# scout_schematics_v0.net
KiCad netlist of a schematic drawn in EAGLE
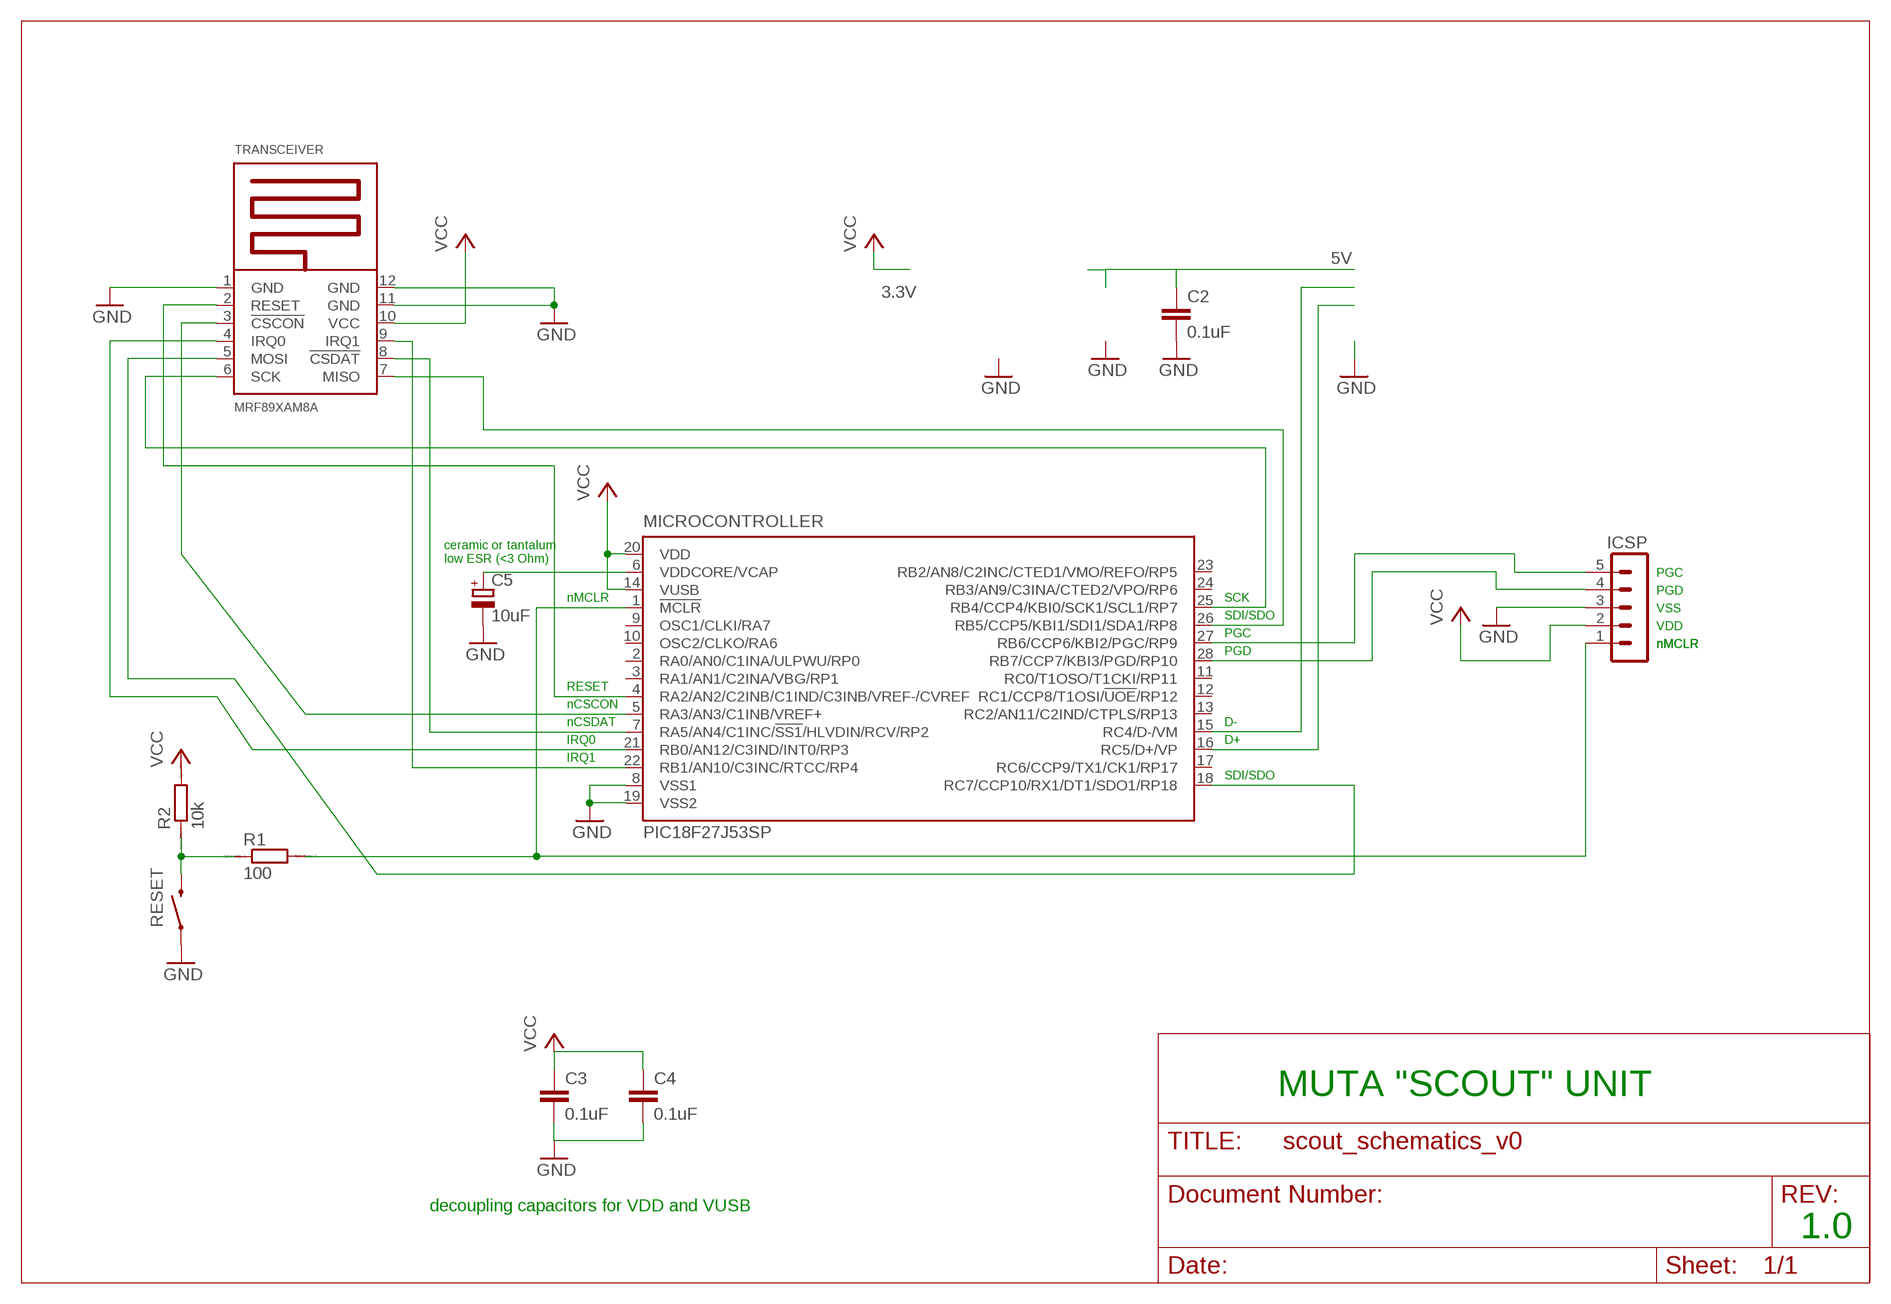
[diagram p0: schematic, sheet 1]

(export (version "E")
  (design (tool "Eeschema 10.0.6"))
  (components
    (comp (ref "C2")
      (value "0.1uF")
      (footprint "eagle-import:C050-025X075")
      (libsource (lib "eagle-import") (part "C-EU050-025X075"))
    )
    (comp (ref "C3")
      (value "0.1uF")
      (footprint "eagle-import:C050-025X075")
      (libsource (lib "eagle-import") (part "C-EU050-025X075"))
    )
    (comp (ref "C4")
      (value "0.1uF")
      (footprint "eagle-import:C050-025X075")
      (libsource (lib "eagle-import") (part "C-EU050-025X075"))
    )
    (comp (ref "C5")
      (value "10uF")
      (footprint "eagle-import:C_6032-28R")
      (libsource (lib "eagle-import") (part "CPOL-EUC/6032-28R"))
    )
    (comp (ref "ICSP")
      (value "MA05-1")
      (footprint "eagle-import:MA05-1")
      (libsource (lib "eagle-import") (part "MA05-1"))
    )
    (comp (ref "MICROCONTROLLER")
      (value "PIC18F27J53SP")
      (footprint "eagle-import:DIL28-3")
      (fields (field (name "MPN") "PIC18F27J53-I/SP"))
      (libsource (lib "eagle-import") (part "PIC18F2J53SP7"))
    )
    (comp (ref "R1")
      (value "100")
      (footprint "eagle-import:0207_10")
      (libsource (lib "eagle-import") (part "R-EU_0207_10"))
    )
    (comp (ref "R2")
      (value "10k")
      (footprint "eagle-import:0207_10")
      (libsource (lib "eagle-import") (part "R-EU_0207_10"))
    )
    (comp (ref "RESET")
      (value "SWITCH-MOMENTARY-2SMD-4")
      (footprint "eagle-import:TACTILE_SWITCH_TALL")
      (libsource (lib "eagle-import") (part "SWITCH-MOMENTARY-2SMD-4"))
    )
    (comp (ref "TRANSCEIVER")
      (value "MRF89XAM8A")
      (footprint "eagle-import:MRF89XAMXA")
      (libsource (lib "eagle-import") (part "MRF89XAM8A"))
    )
  )
  (nets
    (net (code "1") (name "/5V") (class "Default")
      (node (ref "C2") (pin "1") (pinfunction "1_1") (pintype "passive"))
    )
    (net (code "2") (name "GND") (class "Default")
      (node (ref "C2") (pin "2") (pinfunction "2_2") (pintype "passive"))
      (node (ref "C3") (pin "2") (pinfunction "2_2") (pintype "passive"))
      (node (ref "C4") (pin "2") (pinfunction "2_2") (pintype "passive"))
      (node (ref "C5") (pin "-") (pinfunction "-_-") (pintype "passive"))
      (node (ref "ICSP") (pin "3") (pinfunction "3_3") (pintype "passive"))
      (node (ref "MICROCONTROLLER") (pin "19") (pinfunction "VSS2_19") (pintype "input"))
      (node (ref "MICROCONTROLLER") (pin "8") (pinfunction "VSS1_8") (pintype "input"))
      (node (ref "RESET") (pin "A2") (pinfunction "1_A2") (pintype "passive"))
      (node (ref "TRANSCEIVER") (pin "1") (pinfunction "GND_1") (pintype "power_in"))
      (node (ref "TRANSCEIVER") (pin "11") (pinfunction "GND_11") (pintype "power_in"))
      (node (ref "TRANSCEIVER") (pin "12") (pinfunction "GND_12") (pintype "power_in"))
    )
    (net (code "3") (name "Net-(MICROCONTROLLER-RA2{slash}AN2{slash}C2INB{slash}C1IND{slash}C3INB{slash}VREF-{slash}CVREF)") (class "Default")
      (node (ref "MICROCONTROLLER") (pin "4") (pinfunction "RA2/AN2/C2INB/C1IND/C3INB/VREF-/CVREF_4") (pintype "bidirectional"))
      (node (ref "TRANSCEIVER") (pin "2") (pinfunction "RESET_2") (pintype "input"))
    )
    (net (code "4") (name "Net-(MICROCONTROLLER-RA3{slash}AN3{slash}C1INB{slash}VREF+)") (class "Default")
      (node (ref "MICROCONTROLLER") (pin "5") (pinfunction "RA3/AN3/C1INB/VREF+_5") (pintype "bidirectional"))
      (node (ref "TRANSCEIVER") (pin "3") (pinfunction "~{CSCON}_3") (pintype "input"))
    )
    (net (code "5") (name "Net-(MICROCONTROLLER-RA5{slash}AN4{slash}C1INC{slash}~{SS1}{slash}HLVDIN{slash}RCV{slash}RP2)") (class "Default")
      (node (ref "MICROCONTROLLER") (pin "7") (pinfunction "RA5/AN4/C1INC/~{SS1}/HLVDIN/RCV/RP2_7") (pintype "bidirectional"))
      (node (ref "TRANSCEIVER") (pin "8") (pinfunction "~{CSDAT}_8") (pintype "input"))
    )
    (net (code "6") (name "Net-(MICROCONTROLLER-RB0{slash}AN12{slash}C3IND{slash}INT0{slash}RP3)") (class "Default")
      (node (ref "MICROCONTROLLER") (pin "21") (pinfunction "RB0/AN12/C3IND/INT0/RP3_21") (pintype "bidirectional"))
      (node (ref "TRANSCEIVER") (pin "4") (pinfunction "IRQ0_4") (pintype "output"))
    )
    (net (code "7") (name "Net-(MICROCONTROLLER-RB1{slash}AN10{slash}C3INC{slash}RTCC{slash}RP4)") (class "Default")
      (node (ref "MICROCONTROLLER") (pin "22") (pinfunction "RB1/AN10/C3INC/RTCC/RP4_22") (pintype "bidirectional"))
      (node (ref "TRANSCEIVER") (pin "9") (pinfunction "IRQ1_9") (pintype "output"))
    )
    (net (code "8") (name "Net-(MICROCONTROLLER-RB4{slash}CCP4{slash}KBI0{slash}SCK1{slash}SCL1{slash}RP7)") (class "Default")
      (node (ref "MICROCONTROLLER") (pin "25") (pinfunction "RB4/CCP4/KBI0/SCK1/SCL1/RP7_25") (pintype "bidirectional"))
      (node (ref "TRANSCEIVER") (pin "6") (pinfunction "SCK_6") (pintype "input"))
    )
    (net (code "9") (name "Net-(MICROCONTROLLER-RB5{slash}CCP5{slash}KBI1{slash}SDI1{slash}SDA1{slash}RP8)") (class "Default")
      (node (ref "MICROCONTROLLER") (pin "26") (pinfunction "RB5/CCP5/KBI1/SDI1/SDA1/RP8_26") (pintype "bidirectional"))
      (node (ref "TRANSCEIVER") (pin "7") (pinfunction "MISO_7") (pintype "output"))
    )
    (net (code "10") (name "Net-(MICROCONTROLLER-RB6{slash}CCP6{slash}KBI2{slash}PGC{slash}RP9)") (class "Default")
      (node (ref "ICSP") (pin "5") (pinfunction "5_5") (pintype "passive"))
      (node (ref "MICROCONTROLLER") (pin "27") (pinfunction "RB6/CCP6/KBI2/PGC/RP9_27") (pintype "bidirectional"))
    )
    (net (code "11") (name "Net-(MICROCONTROLLER-RB7{slash}CCP7{slash}KBI3{slash}PGD{slash}RP10)") (class "Default")
      (node (ref "ICSP") (pin "4") (pinfunction "4_4") (pintype "passive"))
      (node (ref "MICROCONTROLLER") (pin "28") (pinfunction "RB7/CCP7/KBI3/PGD/RP10_28") (pintype "bidirectional"))
    )
    (net (code "12") (name "Net-(MICROCONTROLLER-RC7{slash}CCP10{slash}RX1{slash}DT1{slash}SDO1{slash}RP18)") (class "Default")
      (node (ref "MICROCONTROLLER") (pin "18") (pinfunction "RC7/CCP10/RX1/DT1/SDO1/RP18_18") (pintype "bidirectional"))
      (node (ref "TRANSCEIVER") (pin "5") (pinfunction "MOSI_5") (pintype "input"))
    )
    (net (code "13") (name "Net-(MICROCONTROLLER-VDDCORE{slash}VCAP)") (class "Default")
      (node (ref "C5") (pin "+") (pinfunction "+_+") (pintype "passive"))
      (node (ref "MICROCONTROLLER") (pin "6") (pinfunction "VDDCORE/VCAP_6") (pintype "input"))
    )
    (net (code "14") (name "Net-(MICROCONTROLLER-~{MCLR})") (class "Default")
      (node (ref "ICSP") (pin "1") (pinfunction "1_1") (pintype "passive"))
      (node (ref "MICROCONTROLLER") (pin "1") (pinfunction "~{MCLR}_1") (pintype "input"))
      (node (ref "R1") (pin "2") (pinfunction "2_2") (pintype "passive"))
    )
    (net (code "15") (name "Net-(RESET-2)") (class "Default")
      (node (ref "R1") (pin "1") (pinfunction "1_1") (pintype "passive"))
      (node (ref "R2") (pin "1") (pinfunction "1_1") (pintype "passive"))
      (node (ref "RESET") (pin "B2") (pinfunction "2_B2") (pintype "passive"))
    )
    (net (code "16") (name "VCC") (class "Default")
      (node (ref "C3") (pin "1") (pinfunction "1_1") (pintype "passive"))
      (node (ref "C4") (pin "1") (pinfunction "1_1") (pintype "passive"))
      (node (ref "ICSP") (pin "2") (pinfunction "2_2") (pintype "passive"))
      (node (ref "MICROCONTROLLER") (pin "14") (pinfunction "VUSB_14") (pintype "input"))
      (node (ref "MICROCONTROLLER") (pin "20") (pinfunction "VDD_20") (pintype "input"))
      (node (ref "R2") (pin "2") (pinfunction "2_2") (pintype "passive"))
      (node (ref "TRANSCEIVER") (pin "10") (pinfunction "VCC_10") (pintype "power_in"))
    )
    (net (code "17") (name "unconnected-(MICROCONTROLLER-OSC1{slash}CLKI{slash}RA7-Pad9)") (class "Default")
      (node (ref "MICROCONTROLLER") (pin "9") (pinfunction "OSC1/CLKI/RA7_9") (pintype "bidirectional"))
    )
    (net (code "18") (name "unconnected-(MICROCONTROLLER-OSC2{slash}CLKO{slash}RA6-Pad10)") (class "Default")
      (node (ref "MICROCONTROLLER") (pin "10") (pinfunction "OSC2/CLKO/RA6_10") (pintype "bidirectional"))
    )
    (net (code "19") (name "unconnected-(MICROCONTROLLER-RA0{slash}AN0{slash}C1INA{slash}ULPWU{slash}RP0-Pad2)") (class "Default")
      (node (ref "MICROCONTROLLER") (pin "2") (pinfunction "RA0/AN0/C1INA/ULPWU/RP0_2") (pintype "bidirectional"))
    )
    (net (code "20") (name "unconnected-(MICROCONTROLLER-RA1{slash}AN1{slash}C2INA{slash}VBG{slash}RP1-Pad3)") (class "Default")
      (node (ref "MICROCONTROLLER") (pin "3") (pinfunction "RA1/AN1/C2INA/VBG/RP1_3") (pintype "bidirectional"))
    )
    (net (code "21") (name "unconnected-(MICROCONTROLLER-RB2{slash}AN8{slash}C2INC{slash}CTED1{slash}VMO{slash}REFO{slash}RP5-Pad23)") (class "Default")
      (node (ref "MICROCONTROLLER") (pin "23") (pinfunction "RB2/AN8/C2INC/CTED1/VMO/REFO/RP5_23") (pintype "bidirectional"))
    )
    (net (code "22") (name "unconnected-(MICROCONTROLLER-RB3{slash}AN9{slash}C3INA{slash}CTED2{slash}VPO{slash}RP6-Pad24)") (class "Default")
      (node (ref "MICROCONTROLLER") (pin "24") (pinfunction "RB3/AN9/C3INA/CTED2/VPO/RP6_24") (pintype "bidirectional"))
    )
    (net (code "23") (name "unconnected-(MICROCONTROLLER-RC0{slash}T1OSO{slash}T1CKI{slash}RP11-Pad11)") (class "Default")
      (node (ref "MICROCONTROLLER") (pin "11") (pinfunction "RC0/T1OSO/T1CKI/RP11_11") (pintype "bidirectional"))
    )
    (net (code "24") (name "unconnected-(MICROCONTROLLER-RC1{slash}CCP8{slash}T1OSI{slash}~{UOE}{slash}RP12-Pad12)") (class "Default")
      (node (ref "MICROCONTROLLER") (pin "12") (pinfunction "RC1/CCP8/T1OSI/~{UOE}/RP12_12") (pintype "bidirectional"))
    )
    (net (code "25") (name "unconnected-(MICROCONTROLLER-RC2{slash}AN11{slash}C2IND{slash}CTPLS{slash}RP13-Pad13)") (class "Default")
      (node (ref "MICROCONTROLLER") (pin "13") (pinfunction "RC2/AN11/C2IND/CTPLS/RP13_13") (pintype "bidirectional"))
    )
    (net (code "26") (name "unconnected-(MICROCONTROLLER-RC4{slash}D-{slash}VM-Pad15)") (class "Default")
      (node (ref "MICROCONTROLLER") (pin "15") (pinfunction "RC4/D-/VM_15") (pintype "bidirectional"))
    )
    (net (code "27") (name "unconnected-(MICROCONTROLLER-RC5{slash}D+{slash}VP-Pad16)") (class "Default")
      (node (ref "MICROCONTROLLER") (pin "16") (pinfunction "RC5/D+/VP_16") (pintype "bidirectional"))
    )
    (net (code "28") (name "unconnected-(MICROCONTROLLER-RC6{slash}CCP9{slash}TX1{slash}CK1{slash}RP17-Pad17)") (class "Default")
      (node (ref "MICROCONTROLLER") (pin "17") (pinfunction "RC6/CCP9/TX1/CK1/RP17_17") (pintype "bidirectional"))
    )
  )
)
